# Moteino.net
KiCad netlist of a schematic drawn in EAGLE
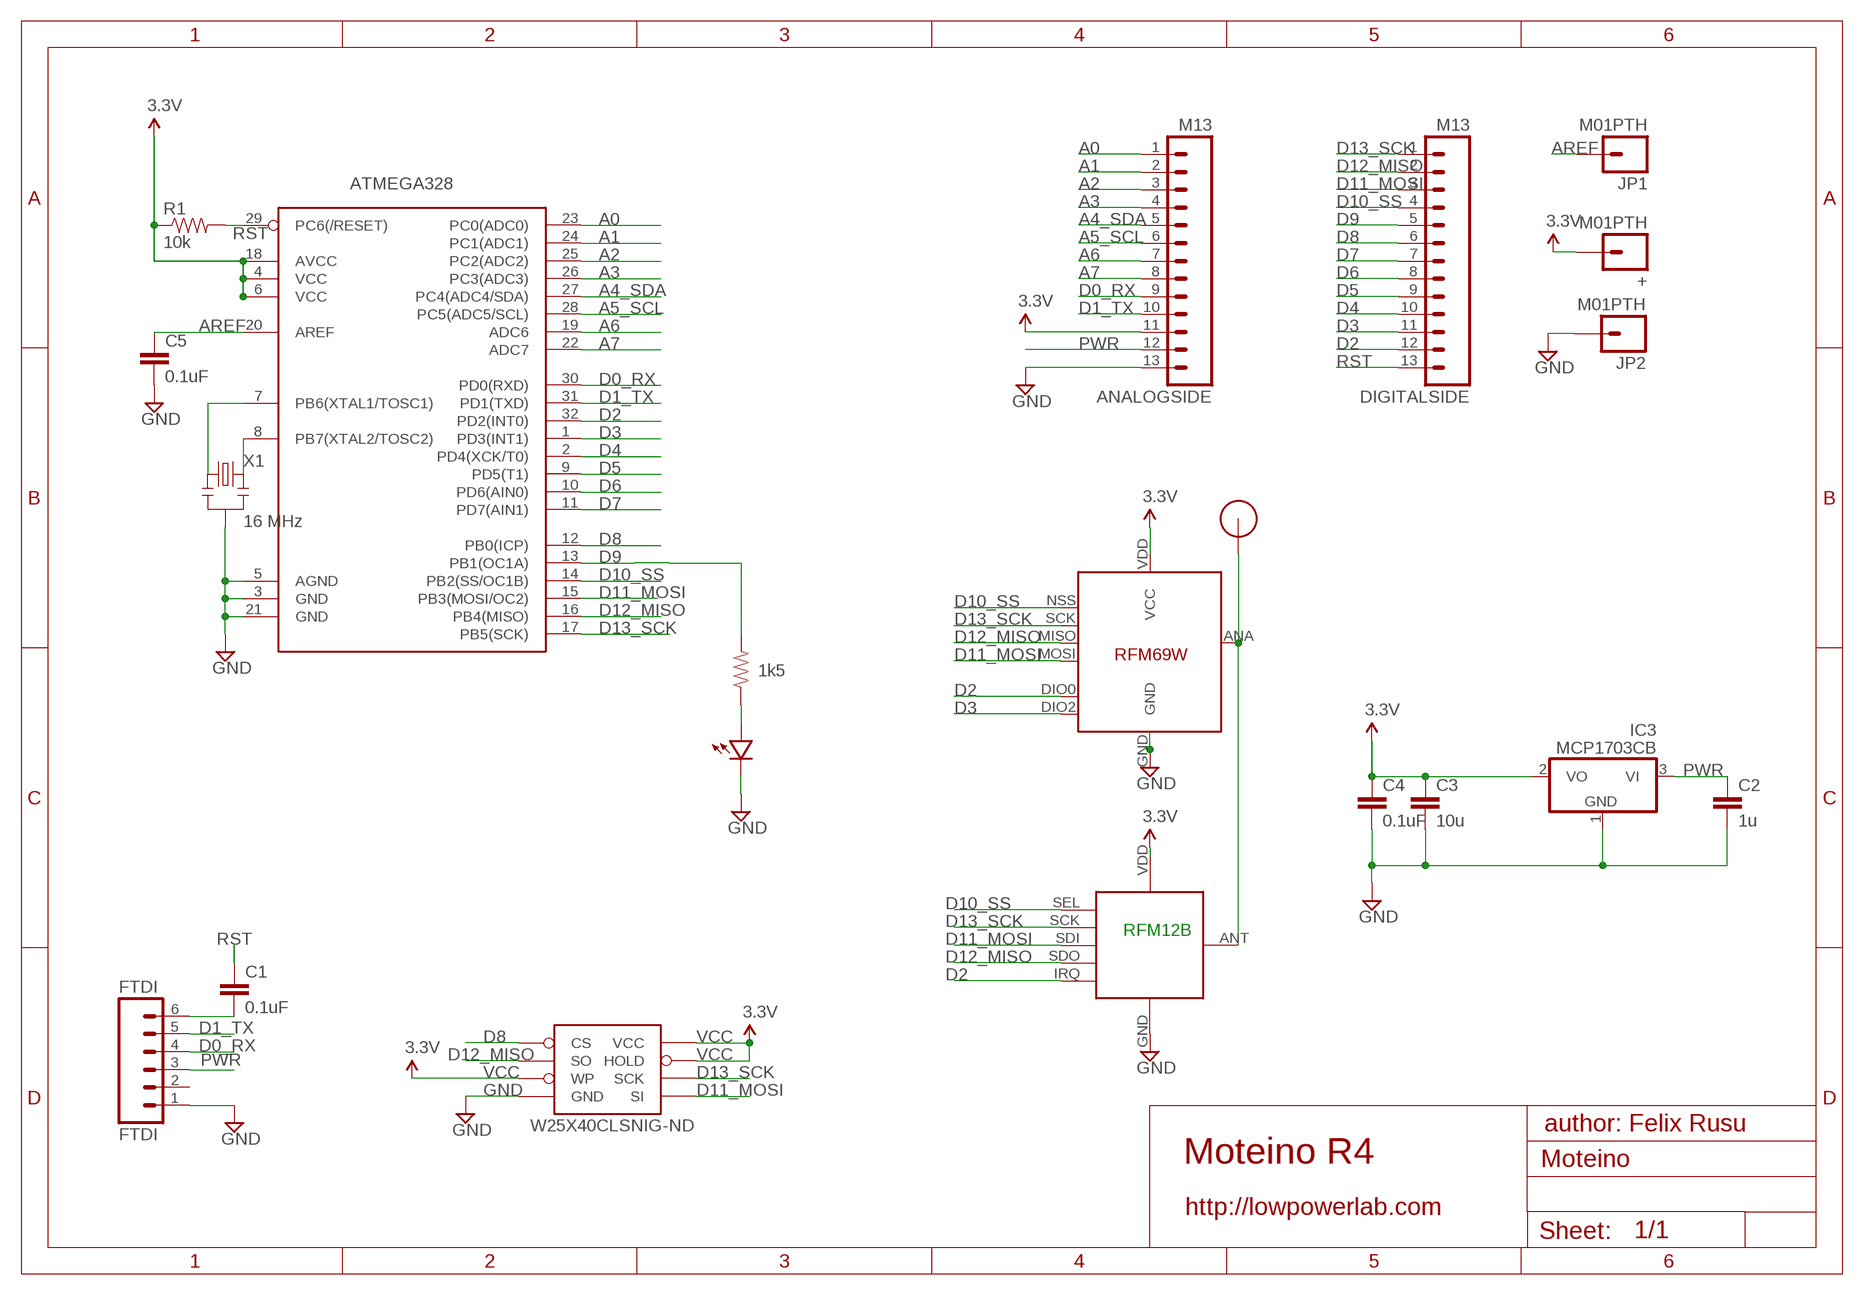
[diagram p0: schematic, sheet 1]

(export (version "E")
  (design (tool "Eeschema 10.0.6"))
  (components
    (comp (ref "+")
      (value "M01PTH")
      (footprint "eagle-import:1X01")
      (libsource (lib "eagle-import") (part "M01PTH"))
    )
    (comp (ref "ANALOGSIDE")
      (value "M13")
      (footprint "eagle-import:1X13")
      (libsource (lib "eagle-import") (part "M13"))
    )
    (comp (ref "ATMEGA328")
      (value "ATMega-328")
      (footprint "eagle-import:TQFP32-08")
      (libsource (lib "eagle-import") (part "ATMEGA168/328TQFP32"))
    )
    (comp (ref "C1")
      (value "0.1uF")
      (footprint "eagle-import:0603-CAP")
      (libsource (lib "eagle-import") (part "CAP0603-CAP"))
    )
    (comp (ref "C2")
      (value "1u")
      (footprint "eagle-import:0603-CAP")
      (libsource (lib "eagle-import") (part "CAP0603-CAP"))
    )
    (comp (ref "C3")
      (value "10u")
      (footprint "eagle-import:0805-CAP")
      (libsource (lib "eagle-import") (part "CAP0805-CAP"))
    )
    (comp (ref "C4")
      (value "0.1uF")
      (footprint "eagle-import:0603-CAP")
      (libsource (lib "eagle-import") (part "CAP0603-CAP"))
    )
    (comp (ref "C5")
      (value "0.1uF")
      (footprint "eagle-import:0603-CAP")
      (libsource (lib "eagle-import") (part "CAP0603-CAP"))
    )
    (comp (ref "DIGITALSIDE")
      (value "M13")
      (footprint "eagle-import:1X13")
      (libsource (lib "eagle-import") (part "M13"))
    )
    (comp (ref "FTDI")
      (value "FTDI")
      (footprint "eagle-import:1X06")
      (libsource (lib "eagle-import") (part "M06SIP"))
    )
    (comp (ref "IC3")
      (value "MCP1703CB")
      (footprint "eagle-import:SOT23")
      (libsource (lib "eagle-import") (part "MCP1703CB"))
    )
    (comp (ref "JP1")
      (value "M01PTH")
      (footprint "eagle-import:1X01")
      (libsource (lib "eagle-import") (part "M01PTH"))
    )
    (comp (ref "JP2")
      (value "M01PTH")
      (footprint "eagle-import:1X01")
      (libsource (lib "eagle-import") (part "M01PTH"))
    )
    (comp (ref "R1")
      (value "10k")
      (footprint "eagle-import:0603-RES")
      (libsource (lib "eagle-import") (part "RESISTOR0603-RES"))
    )
    (comp (ref "R2")
      (value "1k5")
      (footprint "eagle-import:0603-RES")
      (libsource (lib "eagle-import") (part "RESISTOR0603-RES"))
    )
    (comp (ref "RFM12B")
      (value "RFM12B_MINPADS")
      (footprint "eagle-import:RFM12B-MINPADS")
      (libsource (lib "eagle-import") (part "RFM12B_MINPADS"))
    )
    (comp (ref "U$1")
      (value "RFM12B_ANTENNA")
      (footprint "eagle-import:RFM12B-ANTENNA")
      (libsource (lib "eagle-import") (part "RFM12B_ANTENNA"))
    )
    (comp (ref "U$2")
      (value "LED0603")
      (footprint "eagle-import:0603-LED")
      (libsource (lib "eagle-import") (part "LED0603"))
    )
    (comp (ref "U$5")
      (value "RFM69")
      (footprint "eagle-import:RFM69W-MINPADS")
      (libsource (lib "eagle-import") (part "RFM69"))
    )
    (comp (ref "W25X40CLSNIG-ND")
      (value "AT25F512BWIDE_5.3MM")
      (footprint "eagle-import:SO08WIDE")
      (libsource (lib "eagle-import") (part "AT25F512BWIDE_5.3MM"))
    )
    (comp (ref "X1")
      (value "16 MHz")
      (footprint "eagle-import:RESONATOR-SMD")
      (libsource (lib "eagle-import") (part "RESONATORSMD"))
    )
  )
  (nets
    (net (code "1") (name "/A0") (class "Default")
      (node (ref "ANALOGSIDE") (pin "1") (pinfunction "1_1") (pintype "passive"))
      (node (ref "ATMEGA328") (pin "23") (pinfunction "PC0(ADC0)_23") (pintype "bidirectional"))
    )
    (net (code "2") (name "/A1") (class "Default")
      (node (ref "ANALOGSIDE") (pin "2") (pinfunction "2_2") (pintype "passive"))
      (node (ref "ATMEGA328") (pin "24") (pinfunction "PC1(ADC1)_24") (pintype "bidirectional"))
    )
    (net (code "3") (name "/A2") (class "Default")
      (node (ref "ANALOGSIDE") (pin "3") (pinfunction "3_3") (pintype "passive"))
      (node (ref "ATMEGA328") (pin "25") (pinfunction "PC2(ADC2)_25") (pintype "bidirectional"))
    )
    (net (code "4") (name "/A3") (class "Default")
      (node (ref "ANALOGSIDE") (pin "4") (pinfunction "4_4") (pintype "passive"))
      (node (ref "ATMEGA328") (pin "26") (pinfunction "PC3(ADC3)_26") (pintype "bidirectional"))
    )
    (net (code "5") (name "/A4_SDA") (class "Default")
      (node (ref "ANALOGSIDE") (pin "5") (pinfunction "5_5") (pintype "passive"))
      (node (ref "ATMEGA328") (pin "27") (pinfunction "PC4(ADC4/SDA)_27") (pintype "bidirectional"))
    )
    (net (code "6") (name "/A5_SCL") (class "Default")
      (node (ref "ANALOGSIDE") (pin "6") (pinfunction "6_6") (pintype "passive"))
      (node (ref "ATMEGA328") (pin "28") (pinfunction "PC5(ADC5/SCL)_28") (pintype "bidirectional"))
    )
    (net (code "7") (name "/A6") (class "Default")
      (node (ref "ANALOGSIDE") (pin "7") (pinfunction "7_7") (pintype "passive"))
      (node (ref "ATMEGA328") (pin "19") (pinfunction "ADC6_19") (pintype "bidirectional"))
    )
    (net (code "8") (name "/A7") (class "Default")
      (node (ref "ANALOGSIDE") (pin "8") (pinfunction "8_8") (pintype "passive"))
      (node (ref "ATMEGA328") (pin "22") (pinfunction "ADC7_22") (pintype "bidirectional"))
    )
    (net (code "9") (name "/AREF") (class "Default")
      (node (ref "ATMEGA328") (pin "20") (pinfunction "AREF_20") (pintype "bidirectional"))
      (node (ref "C5") (pin "1") (pinfunction "1_1") (pintype "passive"))
      (node (ref "JP1") (pin "1") (pinfunction "1_1") (pintype "passive"))
    )
    (net (code "10") (name "/D0_RX") (class "Default")
      (node (ref "ANALOGSIDE") (pin "9") (pinfunction "9_9") (pintype "passive"))
      (node (ref "ATMEGA328") (pin "30") (pinfunction "PD0(RXD)_30") (pintype "bidirectional"))
      (node (ref "FTDI") (pin "4") (pinfunction "4_4") (pintype "passive"))
    )
    (net (code "11") (name "/D1_TX") (class "Default")
      (node (ref "ANALOGSIDE") (pin "10") (pinfunction "10_10") (pintype "passive"))
      (node (ref "ATMEGA328") (pin "31") (pinfunction "PD1(TXD)_31") (pintype "bidirectional"))
      (node (ref "FTDI") (pin "5") (pinfunction "5_5") (pintype "passive"))
    )
    (net (code "12") (name "/D2") (class "Default")
      (node (ref "ATMEGA328") (pin "32") (pinfunction "PD2(INT0)_32") (pintype "bidirectional"))
      (node (ref "DIGITALSIDE") (pin "12") (pinfunction "12_12") (pintype "passive"))
      (node (ref "RFM12B") (pin "IRQ") (pinfunction "IRQ_IRQ") (pintype "bidirectional"))
      (node (ref "U$5") (pin "DIO0") (pinfunction "DIO0_DIO0") (pintype "open_collector"))
    )
    (net (code "13") (name "/D3") (class "Default")
      (node (ref "ATMEGA328") (pin "1") (pinfunction "PD3(INT1)_1") (pintype "bidirectional"))
      (node (ref "DIGITALSIDE") (pin "11") (pinfunction "11_11") (pintype "passive"))
      (node (ref "U$5") (pin "DIO2") (pinfunction "DIO2_DIO2") (pintype "open_collector"))
    )
    (net (code "14") (name "/D4") (class "Default")
      (node (ref "ATMEGA328") (pin "2") (pinfunction "PD4(XCK/T0)_2") (pintype "bidirectional"))
      (node (ref "DIGITALSIDE") (pin "10") (pinfunction "10_10") (pintype "passive"))
    )
    (net (code "15") (name "/D5") (class "Default")
      (node (ref "ATMEGA328") (pin "9") (pinfunction "PD5(T1)_9") (pintype "bidirectional"))
      (node (ref "DIGITALSIDE") (pin "9") (pinfunction "9_9") (pintype "passive"))
    )
    (net (code "16") (name "/D6") (class "Default")
      (node (ref "ATMEGA328") (pin "10") (pinfunction "PD6(AIN0)_10") (pintype "bidirectional"))
      (node (ref "DIGITALSIDE") (pin "8") (pinfunction "8_8") (pintype "passive"))
    )
    (net (code "17") (name "/D7") (class "Default")
      (node (ref "ATMEGA328") (pin "11") (pinfunction "PD7(AIN1)_11") (pintype "bidirectional"))
      (node (ref "DIGITALSIDE") (pin "7") (pinfunction "7_7") (pintype "passive"))
    )
    (net (code "18") (name "/D8") (class "Default")
      (node (ref "ATMEGA328") (pin "12") (pinfunction "PB0(ICP)_12") (pintype "bidirectional"))
      (node (ref "DIGITALSIDE") (pin "6") (pinfunction "6_6") (pintype "passive"))
      (node (ref "W25X40CLSNIG-ND") (pin "1") (pinfunction "CS_1") (pintype "bidirectional"))
    )
    (net (code "19") (name "/D9") (class "Default")
      (node (ref "ATMEGA328") (pin "13") (pinfunction "PB1(OC1A)_13") (pintype "bidirectional"))
      (node (ref "DIGITALSIDE") (pin "5") (pinfunction "5_5") (pintype "passive"))
      (node (ref "R2") (pin "2") (pinfunction "2_2") (pintype "passive"))
    )
    (net (code "20") (name "/D10_SS") (class "Default")
      (node (ref "ATMEGA328") (pin "14") (pinfunction "PB2(SS/OC1B)_14") (pintype "bidirectional"))
      (node (ref "DIGITALSIDE") (pin "4") (pinfunction "4_4") (pintype "passive"))
      (node (ref "RFM12B") (pin "SEL") (pinfunction "SEL_SEL") (pintype "bidirectional"))
      (node (ref "U$5") (pin "NSS") (pinfunction "SEL_NSS") (pintype "input"))
    )
    (net (code "21") (name "/D11_MOSI") (class "Default")
      (node (ref "ATMEGA328") (pin "15") (pinfunction "PB3(MOSI/OC2)_15") (pintype "bidirectional"))
      (node (ref "DIGITALSIDE") (pin "3") (pinfunction "3_3") (pintype "passive"))
      (node (ref "RFM12B") (pin "SDI") (pinfunction "SDI/MOSI_SDI") (pintype "bidirectional"))
      (node (ref "U$5") (pin "MOSI") (pinfunction "MOSI_MOSI") (pintype "output"))
      (node (ref "W25X40CLSNIG-ND") (pin "5") (pinfunction "SI_5") (pintype "bidirectional"))
    )
    (net (code "22") (name "/D12_MISO") (class "Default")
      (node (ref "ATMEGA328") (pin "16") (pinfunction "PB4(MISO)_16") (pintype "bidirectional"))
      (node (ref "DIGITALSIDE") (pin "2") (pinfunction "2_2") (pintype "passive"))
      (node (ref "RFM12B") (pin "SDO") (pinfunction "SDO/MISO_SDO") (pintype "bidirectional"))
      (node (ref "U$5") (pin "MISO") (pinfunction "MISO_MISO") (pintype "input"))
      (node (ref "W25X40CLSNIG-ND") (pin "2") (pinfunction "SO_2") (pintype "bidirectional"))
    )
    (net (code "23") (name "/D13_SCK") (class "Default")
      (node (ref "ATMEGA328") (pin "17") (pinfunction "PB5(SCK)_17") (pintype "bidirectional"))
      (node (ref "DIGITALSIDE") (pin "1") (pinfunction "1_1") (pintype "passive"))
      (node (ref "RFM12B") (pin "SCK") (pinfunction "SCK_SCK") (pintype "bidirectional"))
      (node (ref "U$5") (pin "SCK") (pinfunction "SCK_SCK") (pintype "input"))
      (node (ref "W25X40CLSNIG-ND") (pin "6") (pinfunction "SCK_6") (pintype "bidirectional"))
    )
    (net (code "24") (name "/PWR") (class "Default")
      (node (ref "ANALOGSIDE") (pin "12") (pinfunction "12_12") (pintype "passive"))
      (node (ref "C2") (pin "1") (pinfunction "1_1") (pintype "passive"))
      (node (ref "FTDI") (pin "3") (pinfunction "3_3") (pintype "passive"))
      (node (ref "IC3") (pin "3") (pinfunction "VI_3") (pintype "input"))
    )
    (net (code "25") (name "/RST") (class "Default")
      (node (ref "ATMEGA328") (pin "29") (pinfunction "PC6(/RESET)_29") (pintype "bidirectional"))
      (node (ref "C1") (pin "1") (pinfunction "1_1") (pintype "passive"))
      (node (ref "DIGITALSIDE") (pin "13") (pinfunction "13_13") (pintype "passive"))
      (node (ref "R1") (pin "2") (pinfunction "2_2") (pintype "passive"))
    )
    (net (code "26") (name "3.3V") (class "Default")
      (node (ref "+") (pin "1") (pinfunction "1_1") (pintype "passive"))
      (node (ref "ANALOGSIDE") (pin "11") (pinfunction "11_11") (pintype "passive"))
      (node (ref "ATMEGA328") (pin "18") (pinfunction "AVCC_18") (pintype "bidirectional"))
      (node (ref "ATMEGA328") (pin "4") (pinfunction "VCC_4") (pintype "bidirectional"))
      (node (ref "ATMEGA328") (pin "6") (pinfunction "VCC_6") (pintype "bidirectional"))
      (node (ref "C3") (pin "1") (pinfunction "1_1") (pintype "passive"))
      (node (ref "C4") (pin "1") (pinfunction "1_1") (pintype "passive"))
      (node (ref "IC3") (pin "2") (pinfunction "VO_2") (pintype "passive"))
      (node (ref "R1") (pin "1") (pinfunction "1_1") (pintype "passive"))
      (node (ref "RFM12B") (pin "VDD") (pinfunction "VDD_VDD") (pintype "bidirectional"))
      (node (ref "U$5") (pin "VDD") (pinfunction "VCC_VDD") (pintype "power_in"))
      (node (ref "W25X40CLSNIG-ND") (pin "3") (pinfunction "WP_3") (pintype "bidirectional"))
      (node (ref "W25X40CLSNIG-ND") (pin "7") (pinfunction "HOLD_7") (pintype "bidirectional"))
      (node (ref "W25X40CLSNIG-ND") (pin "8") (pinfunction "VCC_8") (pintype "bidirectional"))
    )
    (net (code "27") (name "GND") (class "Default")
      (node (ref "ANALOGSIDE") (pin "13") (pinfunction "13_13") (pintype "passive"))
      (node (ref "ATMEGA328") (pin "21") (pinfunction "GND_21") (pintype "bidirectional"))
      (node (ref "ATMEGA328") (pin "3") (pinfunction "GND_3") (pintype "bidirectional"))
      (node (ref "ATMEGA328") (pin "5") (pinfunction "AGND_5") (pintype "bidirectional"))
      (node (ref "C2") (pin "2") (pinfunction "2_2") (pintype "passive"))
      (node (ref "C3") (pin "2") (pinfunction "2_2") (pintype "passive"))
      (node (ref "C4") (pin "2") (pinfunction "2_2") (pintype "passive"))
      (node (ref "C5") (pin "2") (pinfunction "2_2") (pintype "passive"))
      (node (ref "FTDI") (pin "1") (pinfunction "1_1") (pintype "passive"))
      (node (ref "IC3") (pin "1") (pinfunction "GND_1") (pintype "passive"))
      (node (ref "JP2") (pin "1") (pinfunction "1_1") (pintype "passive"))
      (node (ref "RFM12B") (pin "GND") (pinfunction "GND_GND") (pintype "bidirectional"))
      (node (ref "U$2") (pin "MINUS") (pinfunction "MINUS_MINUS") (pintype "passive"))
      (node (ref "U$5") (pin "GND") (pinfunction "GND_GND") (pintype "power_in"))
      (node (ref "W25X40CLSNIG-ND") (pin "4") (pinfunction "GND_4") (pintype "bidirectional"))
      (node (ref "X1") (pin "2") (pinfunction "2_2") (pintype "passive"))
    )
    (net (code "28") (name "Net-(ATMEGA328-PB6(XTAL1{slash}TOSC1))") (class "Default")
      (node (ref "ATMEGA328") (pin "7") (pinfunction "PB6(XTAL1/TOSC1)_7") (pintype "bidirectional"))
      (node (ref "X1") (pin "1") (pinfunction "1_1") (pintype "passive"))
    )
    (net (code "29") (name "Net-(ATMEGA328-PB7(XTAL2{slash}TOSC2))") (class "Default")
      (node (ref "ATMEGA328") (pin "8") (pinfunction "PB7(XTAL2/TOSC2)_8") (pintype "bidirectional"))
      (node (ref "X1") (pin "3") (pinfunction "3_3") (pintype "passive"))
    )
    (net (code "30") (name "Net-(C1-Pad2)") (class "Default")
      (node (ref "C1") (pin "2") (pinfunction "2_2") (pintype "passive"))
      (node (ref "FTDI") (pin "6") (pinfunction "6_6") (pintype "passive"))
    )
    (net (code "31") (name "Net-(R2-Pad1)") (class "Default")
      (node (ref "R2") (pin "1") (pinfunction "1_1") (pintype "passive"))
      (node (ref "U$2") (pin "PLUS") (pinfunction "PLUS_PLUS") (pintype "passive"))
    )
    (net (code "32") (name "Net-(U$1-1)") (class "Default")
      (node (ref "RFM12B") (pin "ANT") (pinfunction "ANT_ANT") (pintype "bidirectional"))
      (node (ref "U$1") (pin "P$1") (pinfunction "1_P$1") (pintype "bidirectional"))
      (node (ref "U$5") (pin "ANA") (pinfunction "ANT_ANA") (pintype "passive"))
    )
    (net (code "33") (name "unconnected-(FTDI-Pad2)") (class "Default")
      (node (ref "FTDI") (pin "2") (pinfunction "2_2") (pintype "passive"))
    )
  )
)
